# LCD.net
KiCad netlist of a schematic drawn in Altium Designer
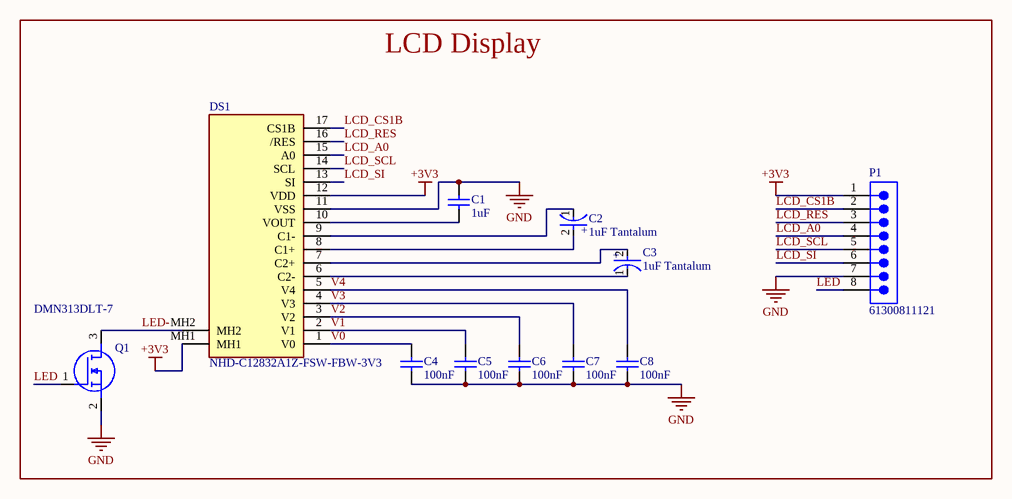
[diagram p0: LCD.SchDoc]

(export (version "E")
  (design (tool "Eeschema 10.0.6"))
  (components
    (comp (ref "C1")
      (value "1uF")
      (footprint "CAPC1206(3216)130_N")
      (description "CAP 1uF 10V ±5% 1206 (3216 Metric) Thickness 1.3mm SMD")
      (fields (field (name "TOLERANCE") "Â±5%"))
      (libsource (lib "Altium Content Vault") (part "CAP"))
    )
    (comp (ref "C2")
      (value "1uF Tantalum")
      (footprint "FP-293DB-MFG")
      (fields (field (name "TOLERANCE") "10%") (field (name "VOLTAGE") "50V"))
      (libsource (lib "Altium Content Vault") (part "a00bbbee19879c290e62620ae7e47b1"))
    )
    (comp (ref "C3")
      (value "1uF Tantalum")
      (footprint "FP-293DB-MFG")
      (fields (field (name "TOLERANCE") "10%") (field (name "VOLTAGE") "50V"))
      (libsource (lib "Altium Content Vault") (part "a00bbbee19879c290e62620ae7e47b1"))
    )
    (comp (ref "C4")
      (value "100nF")
      (footprint "CAPC1608X87X45LL20T05")
      (description "Ceramic 100nF X7R 16V 5%")
      (fields (field (name "PART NUMBER") "C0603X104J4RACTU") (field (name "MANUFACTURER") "Kemet"))
      (libsource (lib "Altium Content Vault") (part "CAP"))
    )
    (comp (ref "C5")
      (value "100nF")
      (footprint "CAPC1608X87X45LL20T05")
      (description "Ceramic 100nF X7R 16V 5%")
      (fields (field (name "PART NUMBER") "C0603X104J4RACTU") (field (name "MANUFACTURER") "Kemet"))
      (libsource (lib "Altium Content Vault") (part "CAP"))
    )
    (comp (ref "C6")
      (value "100nF")
      (footprint "CAPC1608X87X45LL20T05")
      (description "Ceramic 100nF X7R 16V 5%")
      (fields (field (name "PART NUMBER") "C0603X104J4RACTU") (field (name "MANUFACTURER") "Kemet"))
      (libsource (lib "Altium Content Vault") (part "CAP"))
    )
    (comp (ref "C7")
      (value "100nF")
      (footprint "CAPC1608X87X45LL20T05")
      (description "Ceramic 100nF X7R 16V 5%")
      (fields (field (name "PART NUMBER") "C0603X104J4RACTU") (field (name "MANUFACTURER") "Kemet"))
      (libsource (lib "Altium Content Vault") (part "CAP"))
    )
    (comp (ref "C8")
      (value "100nF")
      (footprint "CAPC1608X87X45LL20T05")
      (description "Ceramic 100nF X7R 16V 5%")
      (fields (field (name "PART NUMBER") "C0603X104J4RACTU") (field (name "MANUFACTURER") "Kemet"))
      (libsource (lib "Altium Content Vault") (part "CAP"))
    )
    (comp (ref "DS1")
      (value "NHD-C12832A1Z-FSW-FBW-3V3")
      (footprint "SamacSys:NHDC12832A1ZFSWFBW3V3")
      (description "Display")
      (fields (field (name "MOUSER PART NUMBER") "763-C12832A1ZFSWFBW3"))
      (libsource (lib "*") (part "NHD-C12832A1Z-FSW-FBW-3V3"))
    )
    (comp (ref "P1")
      (value "61300811121")
      (footprint "61300811121")
      (libsource (lib "Altium Content Vault") (part "Header_Male_1R_08P"))
    )
    (comp (ref "Q1")
      (value "DMN313DLT-7")
      (footprint "SamacSys:SOT50P160X90-3N")
      (description "MOSFET (N-Channel)")
      (fields (field (name "MOUSER PART NUMBER") "621-DMN313DLT-7"))
      (libsource (lib "*") (part "DMN313DLT-7"))
    )
  )
  (nets
    (net (code "1") (name "+3V3") (class "Default")
      (node (ref "DS1") (pin "12") (pinfunction "VDD_12") (pintype "passive"))
      (node (ref "DS1") (pin "MH1") (pinfunction "MH1_MH1") (pintype "passive"))
      (node (ref "P1") (pin "1") (pinfunction "1_1") (pintype "passive"))
    )
    (net (code "2") (name "/LCD_A0") (class "Default")
      (node (ref "DS1") (pin "15") (pinfunction "A0_15") (pintype "passive"))
      (node (ref "P1") (pin "4") (pinfunction "4_4") (pintype "passive"))
    )
    (net (code "3") (name "/LCD_CS1B") (class "Default")
      (node (ref "DS1") (pin "17") (pinfunction "CS1B_17") (pintype "passive"))
      (node (ref "P1") (pin "2") (pinfunction "2_2") (pintype "passive"))
    )
    (net (code "4") (name "/LCD_RES") (class "Default")
      (node (ref "DS1") (pin "16") (pinfunction "/RES_16") (pintype "passive"))
      (node (ref "P1") (pin "3") (pinfunction "3_3") (pintype "passive"))
    )
    (net (code "5") (name "/LCD_SCL") (class "Default")
      (node (ref "DS1") (pin "14") (pinfunction "SCL_14") (pintype "passive"))
      (node (ref "P1") (pin "5") (pinfunction "5_5") (pintype "passive"))
    )
    (net (code "6") (name "/LCD_SI") (class "Default")
      (node (ref "DS1") (pin "13") (pinfunction "SI_13") (pintype "passive"))
      (node (ref "P1") (pin "6") (pinfunction "6_6") (pintype "passive"))
    )
    (net (code "7") (name "/LED") (class "Default")
      (node (ref "P1") (pin "8") (pinfunction "8_8") (pintype "passive"))
      (node (ref "Q1") (pin "1") (pinfunction "G_1") (pintype "passive"))
    )
    (net (code "8") (name "/LED-") (class "Default")
      (node (ref "DS1") (pin "MH2") (pinfunction "MH2_MH2") (pintype "passive"))
      (node (ref "Q1") (pin "3") (pinfunction "D_3") (pintype "passive"))
    )
    (net (code "9") (name "/V0") (class "Default")
      (node (ref "C4") (pin "2") (pinfunction "2_2") (pintype "passive"))
      (node (ref "DS1") (pin "1") (pinfunction "V0_1") (pintype "passive"))
    )
    (net (code "10") (name "/V1") (class "Default")
      (node (ref "C5") (pin "2") (pinfunction "2_2") (pintype "passive"))
      (node (ref "DS1") (pin "2") (pinfunction "V1_2") (pintype "passive"))
    )
    (net (code "11") (name "/V2") (class "Default")
      (node (ref "C6") (pin "2") (pinfunction "2_2") (pintype "passive"))
      (node (ref "DS1") (pin "3") (pinfunction "V2_3") (pintype "passive"))
    )
    (net (code "12") (name "/V3") (class "Default")
      (node (ref "C7") (pin "2") (pinfunction "2_2") (pintype "passive"))
      (node (ref "DS1") (pin "4") (pinfunction "V3_4") (pintype "passive"))
    )
    (net (code "13") (name "/V4") (class "Default")
      (node (ref "C8") (pin "2") (pinfunction "2_2") (pintype "passive"))
      (node (ref "DS1") (pin "5") (pinfunction "V4_5") (pintype "passive"))
    )
    (net (code "14") (name "GND") (class "Default")
      (node (ref "C1") (pin "2") (pinfunction "2_2") (pintype "passive"))
      (node (ref "C4") (pin "1") (pinfunction "1_1") (pintype "passive"))
      (node (ref "C5") (pin "1") (pinfunction "1_1") (pintype "passive"))
      (node (ref "C6") (pin "1") (pinfunction "1_1") (pintype "passive"))
      (node (ref "C7") (pin "1") (pinfunction "1_1") (pintype "passive"))
      (node (ref "C8") (pin "1") (pinfunction "1_1") (pintype "passive"))
      (node (ref "DS1") (pin "11") (pinfunction "VSS_11") (pintype "passive"))
      (node (ref "P1") (pin "7") (pinfunction "7_7") (pintype "passive"))
      (node (ref "Q1") (pin "2") (pinfunction "S_2") (pintype "passive"))
    )
    (net (code "15") (name "Net-(C2-A)") (class "Default")
      (node (ref "C2") (pin "2") (pinfunction "A_2") (pintype "passive"))
      (node (ref "DS1") (pin "8") (pinfunction "C1+_8") (pintype "passive"))
    )
    (net (code "16") (name "Net-(C2-C)") (class "Default")
      (node (ref "C2") (pin "1") (pinfunction "C_1") (pintype "passive"))
      (node (ref "DS1") (pin "9") (pinfunction "C1-_9") (pintype "passive"))
    )
    (net (code "17") (name "Net-(C3-A)") (class "Default")
      (node (ref "C3") (pin "2") (pinfunction "A_2") (pintype "passive"))
      (node (ref "DS1") (pin "7") (pinfunction "C2+_7") (pintype "passive"))
    )
    (net (code "18") (name "Net-(C3-C)") (class "Default")
      (node (ref "C3") (pin "1") (pinfunction "C_1") (pintype "passive"))
      (node (ref "DS1") (pin "6") (pinfunction "C2-_6") (pintype "passive"))
    )
    (net (code "19") (name "Net-(DS1-VOUT)") (class "Default")
      (node (ref "C1") (pin "1") (pinfunction "1_1") (pintype "passive"))
      (node (ref "DS1") (pin "10") (pinfunction "VOUT_10") (pintype "passive"))
    )
  )
)
